# PowerRailV2.net
KiCad netlist of a schematic drawn in EAGLE
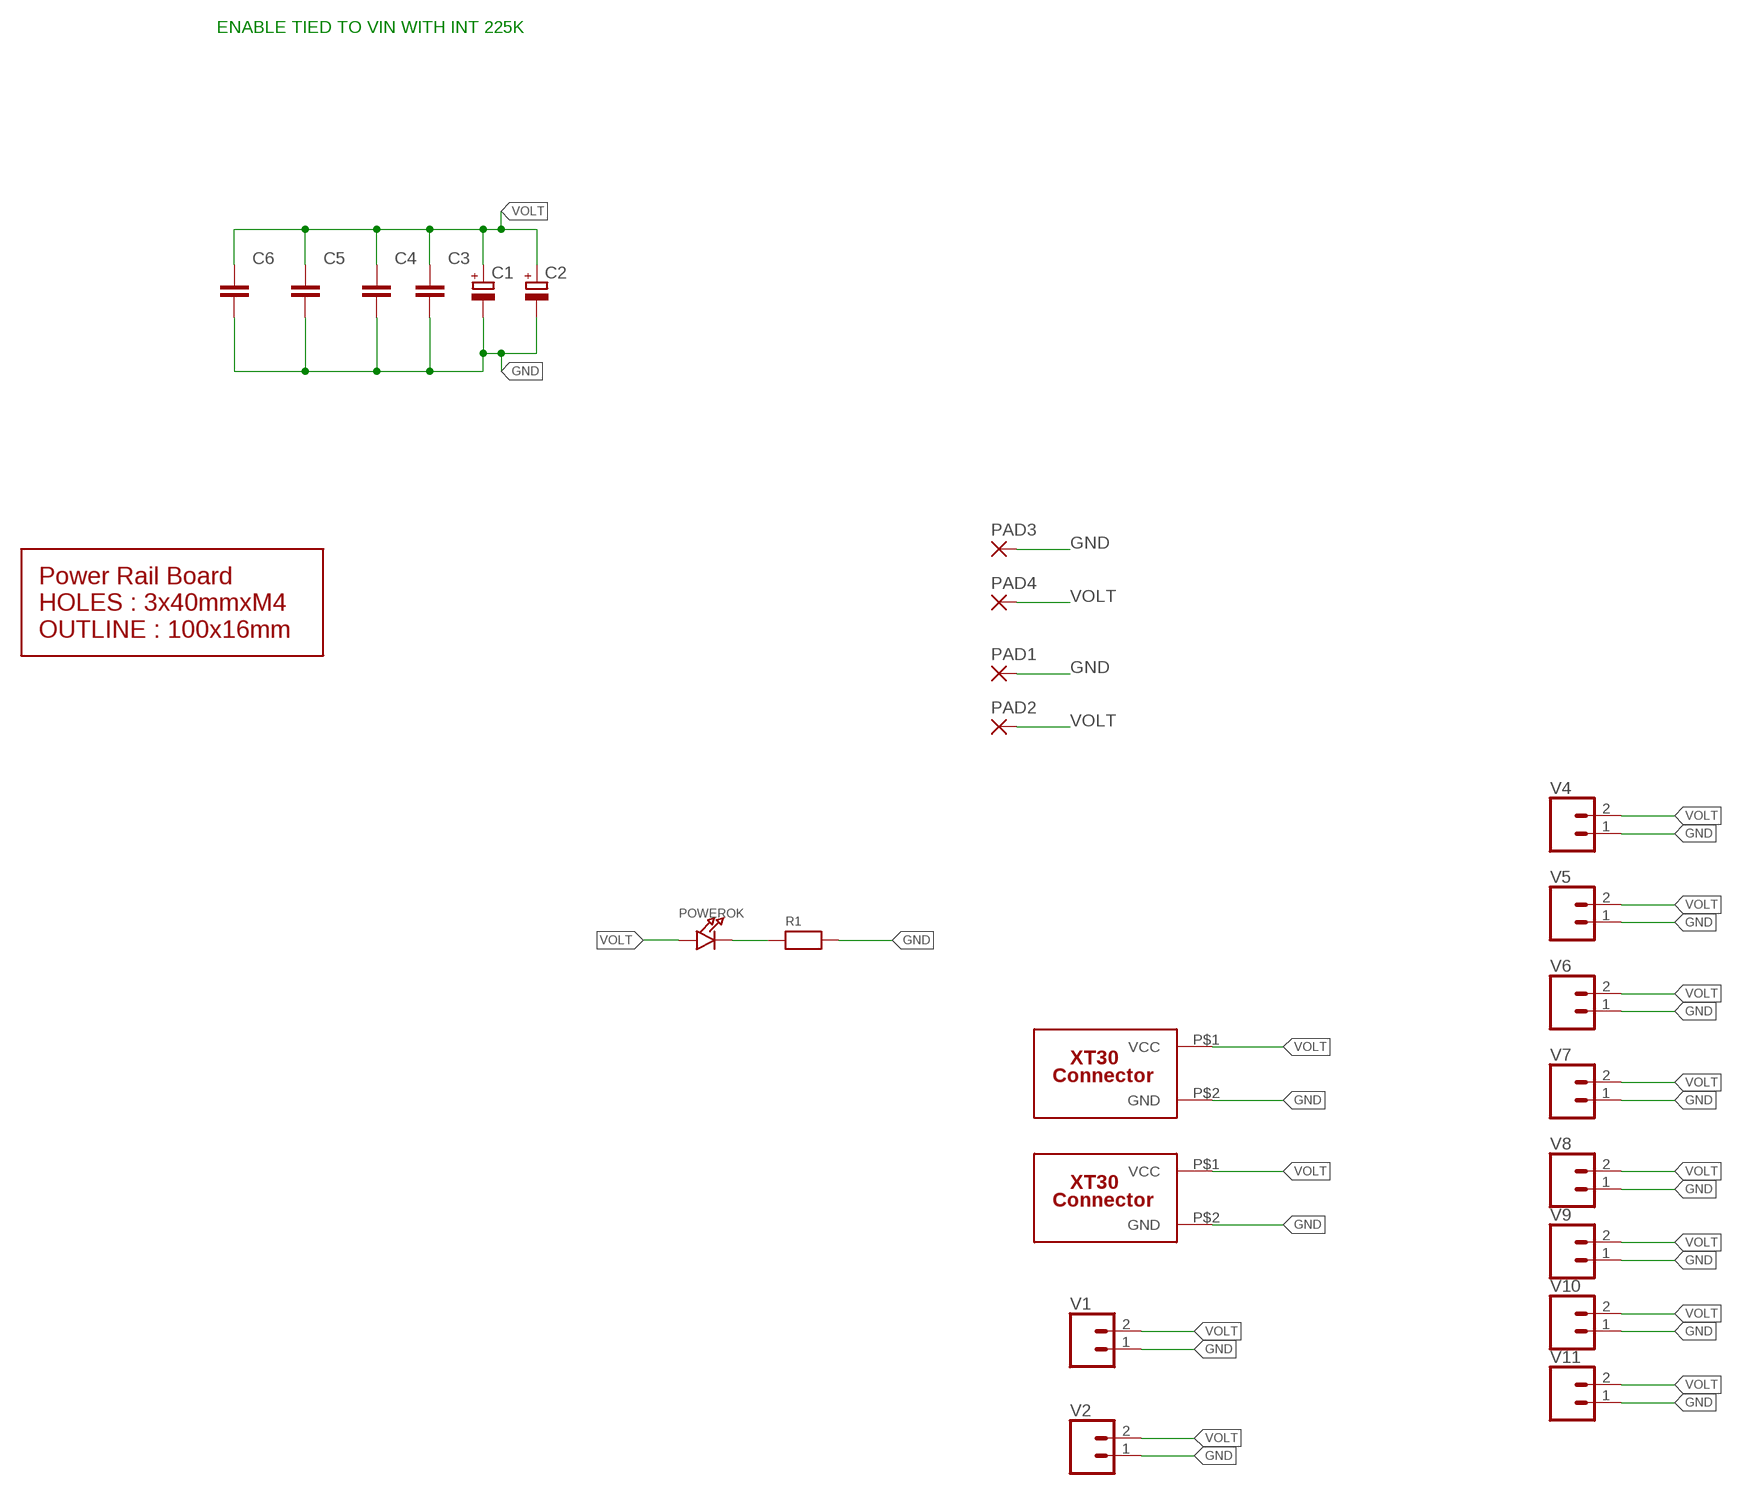
[diagram p0: schematic, sheet 1]

(export (version "E")
  (design (tool "Eeschema 10.0.6"))
  (components
    (comp (ref "C1")
      (value "CPOL-EUE5-6")
      (footprint "eagle-import:E5-6")
      (libsource (lib "eagle-import") (part "CPOL-EUE5-6"))
    )
    (comp (ref "C2")
      (value "CPOL-EUE5-6")
      (footprint "eagle-import:E5-6")
      (libsource (lib "eagle-import") (part "CPOL-EUE5-6"))
    )
    (comp (ref "C3")
      (value "CAPACITOR_NPOL-0805")
      (footprint "eagle-import:C805")
      (libsource (lib "eagle-import") (part "CAPACITOR_NPOL-0805"))
    )
    (comp (ref "C4")
      (value "CAPACITOR_NPOL-0805")
      (footprint "eagle-import:C805")
      (libsource (lib "eagle-import") (part "CAPACITOR_NPOL-0805"))
    )
    (comp (ref "C5")
      (value "CAPACITOR_NPOL-1206")
      (footprint "eagle-import:C1206")
      (libsource (lib "eagle-import") (part "CAPACITOR_NPOL-1206"))
    )
    (comp (ref "C6")
      (value "CAPACITOR_NPOL-1206")
      (footprint "eagle-import:C1206")
      (libsource (lib "eagle-import") (part "CAPACITOR_NPOL-1206"))
    )
    (comp (ref "PAD1")
      (value "SMD2")
      (footprint "eagle-import:SMD1,27-2,54")
      (libsource (lib "eagle-import") (part "SMD2"))
    )
    (comp (ref "PAD2")
      (value "SMD2")
      (footprint "eagle-import:SMD1,27-2,54")
      (libsource (lib "eagle-import") (part "SMD2"))
    )
    (comp (ref "PAD3")
      (value "SMD2")
      (footprint "eagle-import:SMD1,27-2,54")
      (libsource (lib "eagle-import") (part "SMD2"))
    )
    (comp (ref "PAD4")
      (value "SMD2")
      (footprint "eagle-import:SMD1,27-2,54")
      (libsource (lib "eagle-import") (part "SMD2"))
    )
    (comp (ref "POWEROK")
      (value "LED0805")
      (footprint "eagle-import:CHIPLED_0805")
      (libsource (lib "eagle-import") (part "LED0805"))
    )
    (comp (ref "R1")
      (value "RESISTOR0805")
      (footprint "eagle-import:0805")
      (libsource (lib "eagle-import") (part "RESISTOR0805"))
    )
    (comp (ref "U$3")
      (value "BOARD_POWERRAI_PCB")
      (footprint "eagle-import:POWERRAIL_8-LED")
      (libsource (lib "eagle-import") (part "BOARD_POWERRAI_PCB"))
    )
    (comp (ref "U$4")
      (value "XT30")
      (footprint "eagle-import:XT30-VERT")
      (libsource (lib "eagle-import") (part "XT30"))
    )
    (comp (ref "U$6")
      (value "XT30")
      (footprint "eagle-import:XT30-VERT")
      (libsource (lib "eagle-import") (part "XT30"))
    )
    (comp (ref "V1")
      (value "CONN_023.5MM")
      (footprint "eagle-import:SCREWTERMINAL-3.5MM-2")
      (libsource (lib "eagle-import") (part "CONN_023.5MM"))
    )
    (comp (ref "V2")
      (value "CONN_023.5MM")
      (footprint "eagle-import:SCREWTERMINAL-3.5MM-2")
      (libsource (lib "eagle-import") (part "CONN_023.5MM"))
    )
    (comp (ref "V4")
      (value "CONN_023.5MM")
      (footprint "eagle-import:SCREWTERMINAL-3.5MM-2")
      (libsource (lib "eagle-import") (part "CONN_023.5MM"))
    )
    (comp (ref "V5")
      (value "CONN_023.5MM")
      (footprint "eagle-import:SCREWTERMINAL-3.5MM-2")
      (libsource (lib "eagle-import") (part "CONN_023.5MM"))
    )
    (comp (ref "V6")
      (value "CONN_023.5MM")
      (footprint "eagle-import:SCREWTERMINAL-3.5MM-2")
      (libsource (lib "eagle-import") (part "CONN_023.5MM"))
    )
    (comp (ref "V7")
      (value "CONN_023.5MM")
      (footprint "eagle-import:SCREWTERMINAL-3.5MM-2")
      (libsource (lib "eagle-import") (part "CONN_023.5MM"))
    )
    (comp (ref "V8")
      (value "CONN_023.5MM")
      (footprint "eagle-import:SCREWTERMINAL-3.5MM-2")
      (libsource (lib "eagle-import") (part "CONN_023.5MM"))
    )
    (comp (ref "V9")
      (value "CONN_023.5MM")
      (footprint "eagle-import:SCREWTERMINAL-3.5MM-2")
      (libsource (lib "eagle-import") (part "CONN_023.5MM"))
    )
    (comp (ref "V10")
      (value "CONN_023.5MM")
      (footprint "eagle-import:SCREWTERMINAL-3.5MM-2")
      (libsource (lib "eagle-import") (part "CONN_023.5MM"))
    )
    (comp (ref "V11")
      (value "CONN_023.5MM")
      (footprint "eagle-import:SCREWTERMINAL-3.5MM-2")
      (libsource (lib "eagle-import") (part "CONN_023.5MM"))
    )
  )
  (nets
    (net (code "1") (name "GND") (class "Default")
      (node (ref "C1") (pin "-") (pinfunction "-_-") (pintype "passive"))
      (node (ref "C2") (pin "-") (pinfunction "-_-") (pintype "passive"))
      (node (ref "C3") (pin "2") (pinfunction "2_2") (pintype "passive"))
      (node (ref "C4") (pin "2") (pinfunction "2_2") (pintype "passive"))
      (node (ref "C5") (pin "2") (pinfunction "2_2") (pintype "passive"))
      (node (ref "C6") (pin "2") (pinfunction "2_2") (pintype "passive"))
      (node (ref "PAD1") (pin "1") (pinfunction "P_1") (pintype "passive"))
      (node (ref "PAD3") (pin "1") (pinfunction "P_1") (pintype "passive"))
      (node (ref "R1") (pin "2") (pinfunction "2_2") (pintype "passive"))
      (node (ref "U$4") (pin "P$2") (pinfunction "GND_P$2") (pintype "bidirectional"))
      (node (ref "U$6") (pin "P$2") (pinfunction "GND_P$2") (pintype "bidirectional"))
      (node (ref "V1") (pin "1") (pinfunction "1_1") (pintype "passive"))
      (node (ref "V10") (pin "1") (pinfunction "1_1") (pintype "passive"))
      (node (ref "V11") (pin "1") (pinfunction "1_1") (pintype "passive"))
      (node (ref "V2") (pin "1") (pinfunction "1_1") (pintype "passive"))
      (node (ref "V4") (pin "1") (pinfunction "1_1") (pintype "passive"))
      (node (ref "V5") (pin "1") (pinfunction "1_1") (pintype "passive"))
      (node (ref "V6") (pin "1") (pinfunction "1_1") (pintype "passive"))
      (node (ref "V7") (pin "1") (pinfunction "1_1") (pintype "passive"))
      (node (ref "V8") (pin "1") (pinfunction "1_1") (pintype "passive"))
      (node (ref "V9") (pin "1") (pinfunction "1_1") (pintype "passive"))
    )
    (net (code "2") (name "Net-(POWEROK-PadC)") (class "Default")
      (node (ref "POWEROK") (pin "C") (pinfunction "C_C") (pintype "passive"))
      (node (ref "R1") (pin "1") (pinfunction "1_1") (pintype "passive"))
    )
    (net (code "3") (name "VOLT") (class "Default")
      (node (ref "C1") (pin "+") (pinfunction "+_+") (pintype "passive"))
      (node (ref "C2") (pin "+") (pinfunction "+_+") (pintype "passive"))
      (node (ref "C3") (pin "1") (pinfunction "1_1") (pintype "passive"))
      (node (ref "C4") (pin "1") (pinfunction "1_1") (pintype "passive"))
      (node (ref "C5") (pin "1") (pinfunction "1_1") (pintype "passive"))
      (node (ref "C6") (pin "1") (pinfunction "1_1") (pintype "passive"))
      (node (ref "PAD2") (pin "1") (pinfunction "P_1") (pintype "passive"))
      (node (ref "PAD4") (pin "1") (pinfunction "P_1") (pintype "passive"))
      (node (ref "POWEROK") (pin "A") (pinfunction "A_A") (pintype "passive"))
      (node (ref "U$4") (pin "P$1") (pinfunction "VCC_P$1") (pintype "bidirectional"))
      (node (ref "U$6") (pin "P$1") (pinfunction "VCC_P$1") (pintype "bidirectional"))
      (node (ref "V1") (pin "2") (pinfunction "2_2") (pintype "passive"))
      (node (ref "V10") (pin "2") (pinfunction "2_2") (pintype "passive"))
      (node (ref "V11") (pin "2") (pinfunction "2_2") (pintype "passive"))
      (node (ref "V2") (pin "2") (pinfunction "2_2") (pintype "passive"))
      (node (ref "V4") (pin "2") (pinfunction "2_2") (pintype "passive"))
      (node (ref "V5") (pin "2") (pinfunction "2_2") (pintype "passive"))
      (node (ref "V6") (pin "2") (pinfunction "2_2") (pintype "passive"))
      (node (ref "V7") (pin "2") (pinfunction "2_2") (pintype "passive"))
      (node (ref "V8") (pin "2") (pinfunction "2_2") (pintype "passive"))
      (node (ref "V9") (pin "2") (pinfunction "2_2") (pintype "passive"))
    )
  )
)
